# untitled.net
KiCad netlist of a schematic drawn in EAGLE
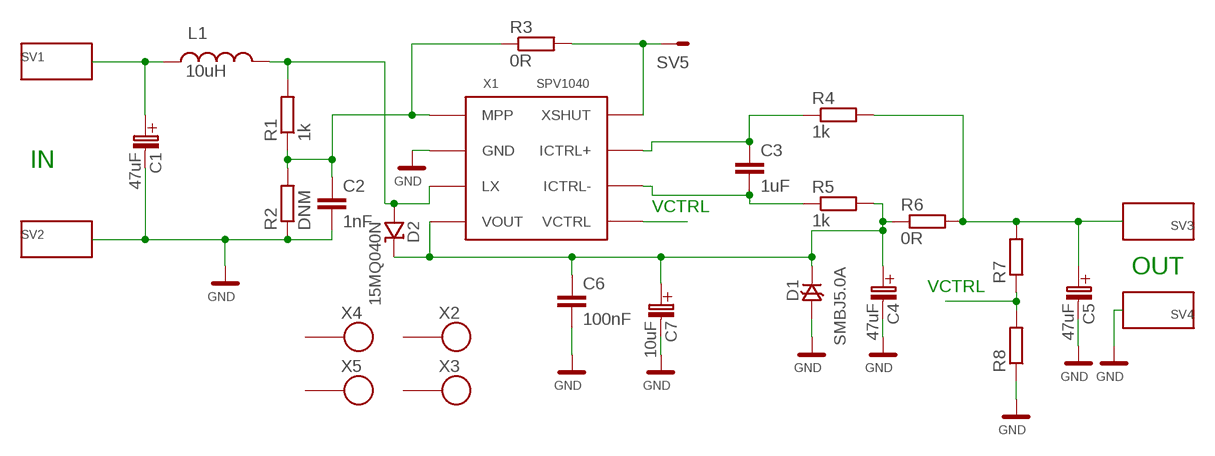
[diagram p0: schematic, sheet 1]

(export (version "E")
  (design (tool "Eeschema 10.0.6"))
  (components
    (comp (ref "C1") (value "47uF") (footprint "eagle-import:C") (libsource (lib "eagle-import") (part "C")))
    (comp (ref "C2")
      (value "1nF")
      (footprint "eagle-import:C0805")
      (libsource (lib "eagle-import") (part "C0805"))
    )
    (comp (ref "C3")
      (value "1uF")
      (footprint "eagle-import:C0805")
      (libsource (lib "eagle-import") (part "C0805"))
    )
    (comp (ref "C4") (value "47uF") (footprint "eagle-import:C") (libsource (lib "eagle-import") (part "C")))
    (comp (ref "C5") (value "47uF") (footprint "eagle-import:C") (libsource (lib "eagle-import") (part "C")))
    (comp (ref "C6")
      (value "100nF")
      (footprint "eagle-import:C0805")
      (libsource (lib "eagle-import") (part "C0805"))
    )
    (comp (ref "C7") (value "10uF") (footprint "eagle-import:B") (libsource (lib "eagle-import") (part "B")))
    (comp (ref "D1")
      (value "SMBJ5.0A")
      (footprint "eagle-import:SMB")
      (libsource (lib "eagle-import") (part "D-TRANSIL"))
    )
    (comp (ref "D2")
      (value "15MQ040N")
      (footprint "eagle-import:SMA")
      (libsource (lib "eagle-import") (part "D-SHOTKY-SMA"))
    )
    (comp (ref "L1")
      (value "10uH")
      (footprint "eagle-import:DE1205-10")
      (libsource (lib "eagle-import") (part "DE1205-10"))
    )
    (comp (ref "R1")
      (value "1k")
      (footprint "eagle-import:0805")
      (libsource (lib "eagle-import") (part "R0805"))
    )
    (comp (ref "R2")
      (value "DNM")
      (footprint "eagle-import:0805")
      (libsource (lib "eagle-import") (part "R0805"))
    )
    (comp (ref "R3")
      (value "0R")
      (footprint "eagle-import:1206")
      (libsource (lib "eagle-import") (part "R1206"))
    )
    (comp (ref "R4")
      (value "1k")
      (footprint "eagle-import:0805")
      (libsource (lib "eagle-import") (part "R0805"))
    )
    (comp (ref "R5")
      (value "1k")
      (footprint "eagle-import:0805")
      (libsource (lib "eagle-import") (part "R0805"))
    )
    (comp (ref "R6")
      (value "0R")
      (footprint "eagle-import:1206")
      (libsource (lib "eagle-import") (part "R1206"))
    )
    (comp (ref "R7")
      (value "R0805")
      (footprint "eagle-import:0805")
      (libsource (lib "eagle-import") (part "R0805"))
    )
    (comp (ref "R8")
      (value "R0805")
      (footprint "eagle-import:0805")
      (libsource (lib "eagle-import") (part "R0805"))
    )
    (comp (ref "SV1")
      (value "WAGO256")
      (footprint "eagle-import:WAGO256")
      (libsource (lib "eagle-import") (part "WAGO256"))
    )
    (comp (ref "SV2")
      (value "WAGO256")
      (footprint "eagle-import:WAGO256")
      (libsource (lib "eagle-import") (part "WAGO256"))
    )
    (comp (ref "SV3")
      (value "WAGO256")
      (footprint "eagle-import:WAGO256")
      (libsource (lib "eagle-import") (part "WAGO256"))
    )
    (comp (ref "SV4")
      (value "WAGO256")
      (footprint "eagle-import:WAGO256")
      (libsource (lib "eagle-import") (part "WAGO256"))
    )
    (comp (ref "SV5")
      (value "MA01-1")
      (footprint "eagle-import:MA01-1")
      (libsource (lib "eagle-import") (part "MA01-1"))
    )
    (comp (ref "X1")
      (value "SPV1040")
      (footprint "eagle-import:TSSOP8")
      (libsource (lib "eagle-import") (part "SPV1040"))
    )
    (comp (ref "X2")
      (value "SROUB3M")
      (footprint "eagle-import:SROUB3M")
      (libsource (lib "eagle-import") (part "SROUB3M"))
    )
    (comp (ref "X3")
      (value "SROUB3M")
      (footprint "eagle-import:SROUB3M")
      (libsource (lib "eagle-import") (part "SROUB3M"))
    )
    (comp (ref "X4")
      (value "SROUB3M")
      (footprint "eagle-import:SROUB3M")
      (libsource (lib "eagle-import") (part "SROUB3M"))
    )
    (comp (ref "X5")
      (value "SROUB3M")
      (footprint "eagle-import:SROUB3M")
      (libsource (lib "eagle-import") (part "SROUB3M"))
    )
  )
  (nets
    (net (code "1") (name "/VCTRL") (class "Default")
      (node (ref "R7") (pin "1") (pinfunction "1_1") (pintype "passive"))
      (node (ref "R8") (pin "2") (pinfunction "2_2") (pintype "passive"))
      (node (ref "X1") (pin "5") (pinfunction "VCTRL_5") (pintype "bidirectional"))
    )
    (net (code "2") (name "GND") (class "Default")
      (node (ref "C1") (pin "-") (pinfunction "C_EL-_-") (pintype "passive"))
      (node (ref "C2") (pin "2") (pinfunction "2_2") (pintype "passive"))
      (node (ref "C4") (pin "-") (pinfunction "C_EL-_-") (pintype "passive"))
      (node (ref "C5") (pin "-") (pinfunction "C_EL-_-") (pintype "passive"))
      (node (ref "C6") (pin "2") (pinfunction "2_2") (pintype "passive"))
      (node (ref "C7") (pin "-") (pinfunction "C_EL-_-") (pintype "passive"))
      (node (ref "D1") (pin "A") (pinfunction "A_A") (pintype "passive"))
      (node (ref "R2") (pin "1") (pinfunction "1_1") (pintype "passive"))
      (node (ref "R8") (pin "1") (pinfunction "1_1") (pintype "passive"))
      (node (ref "SV2") (pin "1") (pinfunction "P$1_1") (pintype "passive"))
      (node (ref "SV2") (pin "A1") (pinfunction "P$1_A1") (pintype "passive"))
      (node (ref "SV4") (pin "1") (pinfunction "P$1_1") (pintype "passive"))
      (node (ref "SV4") (pin "A1") (pinfunction "P$1_A1") (pintype "passive"))
      (node (ref "X1") (pin "2") (pinfunction "GND_2") (pintype "bidirectional"))
    )
    (net (code "3") (name "Net-(C1-C_EL+)") (class "Default")
      (node (ref "C1") (pin "+") (pinfunction "C_EL+_+") (pintype "passive"))
      (node (ref "L1") (pin "P$1") (pinfunction "1_P$1") (pintype "passive"))
      (node (ref "SV1") (pin "1") (pinfunction "P$1_1") (pintype "passive"))
      (node (ref "SV1") (pin "A1") (pinfunction "P$1_A1") (pintype "passive"))
    )
    (net (code "4") (name "Net-(C4-C_EL+)") (class "Default")
      (node (ref "C4") (pin "+") (pinfunction "C_EL+_+") (pintype "passive"))
      (node (ref "C6") (pin "1") (pinfunction "1_1") (pintype "passive"))
      (node (ref "C7") (pin "+") (pinfunction "C_EL+_+") (pintype "passive"))
      (node (ref "D1") (pin "K") (pinfunction "K_K") (pintype "passive"))
      (node (ref "D2") (pin "K") (pinfunction "K_K") (pintype "passive"))
      (node (ref "R5") (pin "2") (pinfunction "2_2") (pintype "passive"))
      (node (ref "R6") (pin "1") (pinfunction "1_1") (pintype "passive"))
      (node (ref "X1") (pin "4") (pinfunction "VOUT_4") (pintype "bidirectional"))
    )
    (net (code "5") (name "Net-(C5-C_EL+)") (class "Default")
      (node (ref "C5") (pin "+") (pinfunction "C_EL+_+") (pintype "passive"))
      (node (ref "R4") (pin "2") (pinfunction "2_2") (pintype "passive"))
      (node (ref "R6") (pin "2") (pinfunction "2_2") (pintype "passive"))
      (node (ref "R7") (pin "2") (pinfunction "2_2") (pintype "passive"))
      (node (ref "SV3") (pin "1") (pinfunction "P$1_1") (pintype "passive"))
      (node (ref "SV3") (pin "A1") (pinfunction "P$1_A1") (pintype "passive"))
    )
    (net (code "6") (name "Net-(L1-2)") (class "Default")
      (node (ref "D2") (pin "A") (pinfunction "A_A") (pintype "passive"))
      (node (ref "L1") (pin "P$2") (pinfunction "2_P$2") (pintype "passive"))
      (node (ref "R1") (pin "2") (pinfunction "2_2") (pintype "passive"))
      (node (ref "X1") (pin "3") (pinfunction "LX_3") (pintype "bidirectional"))
    )
    (net (code "7") (name "Net-(SV5-P$1)") (class "Default")
      (node (ref "R3") (pin "2") (pinfunction "2_2") (pintype "passive"))
      (node (ref "SV5") (pin "1") (pinfunction "P$1_1") (pintype "passive"))
      (node (ref "X1") (pin "8") (pinfunction "XSHUT_8") (pintype "bidirectional"))
    )
    (net (code "8") (name "Net-(X1-ICTRL+)") (class "Default")
      (node (ref "C3") (pin "1") (pinfunction "1_1") (pintype "passive"))
      (node (ref "R4") (pin "1") (pinfunction "1_1") (pintype "passive"))
      (node (ref "X1") (pin "7") (pinfunction "ICTRL+_7") (pintype "bidirectional"))
    )
    (net (code "9") (name "Net-(X1-ICTRL-)") (class "Default")
      (node (ref "C3") (pin "2") (pinfunction "2_2") (pintype "passive"))
      (node (ref "R5") (pin "1") (pinfunction "1_1") (pintype "passive"))
      (node (ref "X1") (pin "6") (pinfunction "ICTRL-_6") (pintype "bidirectional"))
    )
    (net (code "10") (name "Net-(X1-MPP)") (class "Default")
      (node (ref "C2") (pin "1") (pinfunction "1_1") (pintype "passive"))
      (node (ref "R1") (pin "1") (pinfunction "1_1") (pintype "passive"))
      (node (ref "R2") (pin "2") (pinfunction "2_2") (pintype "passive"))
      (node (ref "R3") (pin "1") (pinfunction "1_1") (pintype "passive"))
      (node (ref "X1") (pin "1") (pinfunction "MPP_1") (pintype "bidirectional"))
    )
    (net (code "11") (name "unconnected-(X2-PadP$1)") (class "Default")
      (node (ref "X2") (pin "P$1") (pinfunction "P$1_P$1") (pintype "bidirectional"))
    )
    (net (code "12") (name "unconnected-(X3-PadP$1)") (class "Default")
      (node (ref "X3") (pin "P$1") (pinfunction "P$1_P$1") (pintype "bidirectional"))
    )
    (net (code "13") (name "unconnected-(X4-PadP$1)") (class "Default")
      (node (ref "X4") (pin "P$1") (pinfunction "P$1_P$1") (pintype "bidirectional"))
    )
    (net (code "14") (name "unconnected-(X5-PadP$1)") (class "Default")
      (node (ref "X5") (pin "P$1") (pinfunction "P$1_P$1") (pintype "bidirectional"))
    )
  )
)
